# Keyboard.net
KiCad netlist of a schematic drawn in Altium Designer
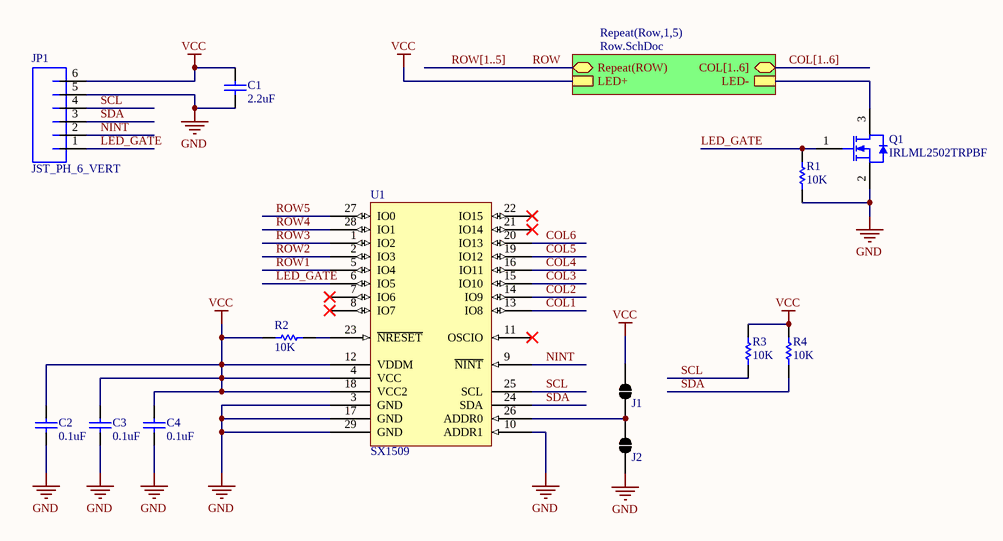
[diagram p0: Keyboard.SchDoc]

(export (version "E")
  (design (tool "Eeschema 10.0.6"))
  (components
    (comp (ref "C1")
      (value "2.2uF")
      (footprint "CAPC0603(1608)100_N")
      (description "CAP 2.2uF 25V ±10% 0603 (1608 Metric) Thickness 1mm SMD")
      (fields (field (name "TOLERANCE") "Â±10%"))
      (libsource (lib "Altium Content Vault") (part "CMP-1035-02767-1"))
    )
    (comp (ref "C2")
      (value "0.1uF")
      (footprint "CAPC0603(1608)100_N")
      (description "CAP 100nF 100V ±10% 0603 (1608 Metric) Thickness 1mm SMD")
      (fields (field (name "TOLERANCE") "Â±10%"))
      (libsource (lib "Altium Content Vault") (part "CAP"))
    )
    (comp (ref "C3")
      (value "0.1uF")
      (footprint "CAPC0603(1608)100_N")
      (description "CAP 100nF 100V ±10% 0603 (1608 Metric) Thickness 1mm SMD")
      (fields (field (name "TOLERANCE") "Â±10%"))
      (libsource (lib "Altium Content Vault") (part "CAP"))
    )
    (comp (ref "C4")
      (value "0.1uF")
      (footprint "CAPC0603(1608)100_N")
      (description "CAP 100nF 100V ±10% 0603 (1608 Metric) Thickness 1mm SMD")
      (fields (field (name "TOLERANCE") "Â±10%"))
      (libsource (lib "Altium Content Vault") (part "CAP"))
    )
    (comp (ref "J1")
      (value "ADDR_H")
      (footprint "SOLDER JUMPER")
      (libsource (lib "Keyboard") (part "Solder Jumper"))
    )
    (comp (ref "J2")
      (value "ADDR_L")
      (footprint "SOLDER JUMPER")
      (libsource (lib "Keyboard") (part "Solder Jumper"))
    )
    (comp (ref "JP1")
      (value "JST_PH_6_VERT")
      (footprint "JST_PH_6_MIRRORABLE")
      (fields
        (field (name "PARTNUMBER") "B6B-PH-K-S(LF)(SN)")
        (field (name "MANUFACTURER") "JST Sales America Inc.")
      )
      (libsource (lib "Keyboard") (part "JST_PH_6_VERT"))
    )
    (comp (ref "Q1")
      (value "IRLML2502TRPBF")
      (footprint "INTR-SOT-23-3_V")
      (description "N-Channel HEXFET(R) Power MOSFET, 20 V VDS, +/- 12 V VGS, 4.2 A, 3-Pin SOT23, RoHS, Tape and Reel")
      (fields (field (name "MANUFACTURER") "International Rectifier"))
      (libsource (lib "Altium Content Vault") (part "NEMOS-GSD-3"))
    )
    (comp (ref "R1")
      (value "10K")
      (footprint "RESC0603(1608)_N")
      (description "10K 0.1W 5% 0603 (1608 Metric)  SMD")
      (fields (field (name "TOLERANCE") "5 %") (field (name "POWER") "0.1 W"))
      (libsource (lib "Altium Content Vault") (part "RES"))
    )
    (comp (ref "R2")
      (value "10K")
      (footprint "RESC0603(1608)_N")
      (description "10K 0.1W 5% 0603 (1608 Metric)  SMD")
      (fields (field (name "TOLERANCE") "5 %") (field (name "POWER") "0.1 W"))
      (libsource (lib "Altium Content Vault") (part "RES"))
    )
    (comp (ref "R3")
      (value "10K")
      (footprint "RESC0603(1608)_N")
      (description "10K 0.1W 5% 0603 (1608 Metric)  SMD")
      (fields (field (name "TOLERANCE") "5 %") (field (name "POWER") "0.1 W"))
      (libsource (lib "Altium Content Vault") (part "RES"))
    )
    (comp (ref "R4")
      (value "10K")
      (footprint "RESC0603(1608)_N")
      (description "10K 0.1W 5% 0603 (1608 Metric)  SMD")
      (fields (field (name "TOLERANCE") "5 %") (field (name "POWER") "0.1 W"))
      (libsource (lib "Altium Content Vault") (part "RES"))
    )
    (comp (ref "U1") (value "SX1509") (footprint "QFN_UT_28") (libsource (lib "Keyboard") (part "SX1509")))
  )
  (nets
    (net (code "1") (name "/COL1") (class "Default")
      (node (ref "U1") (pin "13") (pinfunction "IO8_13") (pintype "bidirectional"))
    )
    (net (code "2") (name "/COL2") (class "Default")
      (node (ref "U1") (pin "14") (pinfunction "IO9_14") (pintype "bidirectional"))
    )
    (net (code "3") (name "/COL3") (class "Default")
      (node (ref "U1") (pin "15") (pinfunction "IO10_15") (pintype "bidirectional"))
    )
    (net (code "4") (name "/COL4") (class "Default")
      (node (ref "U1") (pin "16") (pinfunction "IO11_16") (pintype "bidirectional"))
    )
    (net (code "5") (name "/COL5") (class "Default")
      (node (ref "U1") (pin "19") (pinfunction "IO12_19") (pintype "bidirectional"))
    )
    (net (code "6") (name "/COL6") (class "Default")
      (node (ref "U1") (pin "20") (pinfunction "IO13_20") (pintype "bidirectional"))
    )
    (net (code "8") (name "/LED-") (class "Default")
      (node (ref "Q1") (pin "3") (pinfunction "D_3") (pintype "passive"))
    )
    (net (code "9") (name "/LED_GATE") (class "Default")
      (node (ref "JP1") (pin "1") (pinfunction "1_1") (pintype "passive"))
      (node (ref "Q1") (pin "1") (pinfunction "G_1") (pintype "passive"))
      (node (ref "R1") (pin "2") (pinfunction "2_2") (pintype "passive"))
      (node (ref "U1") (pin "6") (pinfunction "IO5_6") (pintype "bidirectional"))
    )
    (net (code "10") (name "/NINT") (class "Default")
      (node (ref "JP1") (pin "2") (pinfunction "2_2") (pintype "passive"))
      (node (ref "U1") (pin "9") (pinfunction "~{NINT}_9") (pintype "input"))
    )
    (net (code "12") (name "/ROW1") (class "Default")
      (node (ref "U1") (pin "5") (pinfunction "IO4_5") (pintype "bidirectional"))
    )
    (net (code "13") (name "/ROW2") (class "Default")
      (node (ref "U1") (pin "2") (pinfunction "IO3_2") (pintype "bidirectional"))
    )
    (net (code "14") (name "/ROW3") (class "Default")
      (node (ref "U1") (pin "1") (pinfunction "IO2_1") (pintype "bidirectional"))
    )
    (net (code "15") (name "/ROW4") (class "Default")
      (node (ref "U1") (pin "28") (pinfunction "IO1_28") (pintype "bidirectional"))
    )
    (net (code "16") (name "/ROW5") (class "Default")
      (node (ref "U1") (pin "27") (pinfunction "IO0_27") (pintype "bidirectional"))
    )
    (net (code "18") (name "/SCL") (class "Default")
      (node (ref "JP1") (pin "4") (pinfunction "4_4") (pintype "passive"))
      (node (ref "R3") (pin "2") (pinfunction "2_2") (pintype "passive"))
      (node (ref "U1") (pin "25") (pinfunction "SCL_25") (pintype "open_collector"))
    )
    (net (code "19") (name "/SDA") (class "Default")
      (node (ref "JP1") (pin "3") (pinfunction "3_3") (pintype "passive"))
      (node (ref "R4") (pin "2") (pinfunction "2_2") (pintype "passive"))
      (node (ref "U1") (pin "24") (pinfunction "SDA_24") (pintype "open_collector"))
    )
    (net (code "20") (name "GND") (class "Default")
      (node (ref "C1") (pin "2") (pinfunction "2_2") (pintype "passive"))
      (node (ref "C2") (pin "1") (pinfunction "1_1") (pintype "passive"))
      (node (ref "C3") (pin "1") (pinfunction "1_1") (pintype "passive"))
      (node (ref "C4") (pin "1") (pinfunction "1_1") (pintype "passive"))
      (node (ref "J2") (pin "1") (pinfunction "1_1") (pintype "passive"))
      (node (ref "JP1") (pin "5") (pinfunction "5_5") (pintype "passive"))
      (node (ref "Q1") (pin "2") (pinfunction "S_2") (pintype "passive"))
      (node (ref "R1") (pin "1") (pinfunction "1_1") (pintype "passive"))
      (node (ref "U1") (pin "10") (pinfunction "ADDR1_10") (pintype "input"))
      (node (ref "U1") (pin "17") (pinfunction "GND_17") (pintype "power_in"))
      (node (ref "U1") (pin "29") (pinfunction "GND_29") (pintype "power_in"))
      (node (ref "U1") (pin "3") (pinfunction "GND_3") (pintype "power_in"))
    )
    (net (code "21") (name "Net-(U1-ADDR0)") (class "Default")
      (node (ref "J1") (pin "1") (pinfunction "1_1") (pintype "passive"))
      (node (ref "J2") (pin "2") (pinfunction "2_2") (pintype "passive"))
      (node (ref "U1") (pin "26") (pinfunction "ADDR0_26") (pintype "input"))
    )
    (net (code "22") (name "Net-(U1-~{NRESET})") (class "Default")
      (node (ref "R2") (pin "1") (pinfunction "1_1") (pintype "passive"))
      (node (ref "U1") (pin "23") (pinfunction "~{NRESET}_23") (pintype "input"))
    )
    (net (code "23") (name "VCC") (class "Default")
      (node (ref "C1") (pin "1") (pinfunction "1_1") (pintype "passive"))
      (node (ref "C2") (pin "2") (pinfunction "2_2") (pintype "passive"))
      (node (ref "C3") (pin "2") (pinfunction "2_2") (pintype "passive"))
      (node (ref "C4") (pin "2") (pinfunction "2_2") (pintype "passive"))
      (node (ref "J1") (pin "2") (pinfunction "2_2") (pintype "passive"))
      (node (ref "JP1") (pin "6") (pinfunction "6_6") (pintype "passive"))
      (node (ref "R2") (pin "2") (pinfunction "2_2") (pintype "passive"))
      (node (ref "R3") (pin "1") (pinfunction "1_1") (pintype "passive"))
      (node (ref "R4") (pin "1") (pinfunction "1_1") (pintype "passive"))
      (node (ref "U1") (pin "12") (pinfunction "VDDM_12") (pintype "power_in"))
      (node (ref "U1") (pin "18") (pinfunction "VCC2_18") (pintype "power_in"))
      (node (ref "U1") (pin "4") (pinfunction "VCC_4") (pintype "power_in"))
    )
    (net (code "24") (name "unconnected-(U1-IO6-Pad7)") (class "Default")
      (node (ref "U1") (pin "7") (pinfunction "IO6_7") (pintype "bidirectional+no_connect"))
    )
    (net (code "25") (name "unconnected-(U1-IO7-Pad8)") (class "Default")
      (node (ref "U1") (pin "8") (pinfunction "IO7_8") (pintype "bidirectional+no_connect"))
    )
    (net (code "26") (name "unconnected-(U1-IO14-Pad21)") (class "Default")
      (node (ref "U1") (pin "21") (pinfunction "IO14_21") (pintype "bidirectional+no_connect"))
    )
    (net (code "27") (name "unconnected-(U1-IO15-Pad22)") (class "Default")
      (node (ref "U1") (pin "22") (pinfunction "IO15_22") (pintype "bidirectional+no_connect"))
    )
    (net (code "28") (name "unconnected-(U1-OSCIO-Pad11)") (class "Default")
      (node (ref "U1") (pin "11") (pinfunction "OSCIO_11") (pintype "input+no_connect"))
    )
  )
)
